# POWER-12V5V.net
KiCad netlist of a schematic drawn in EAGLE
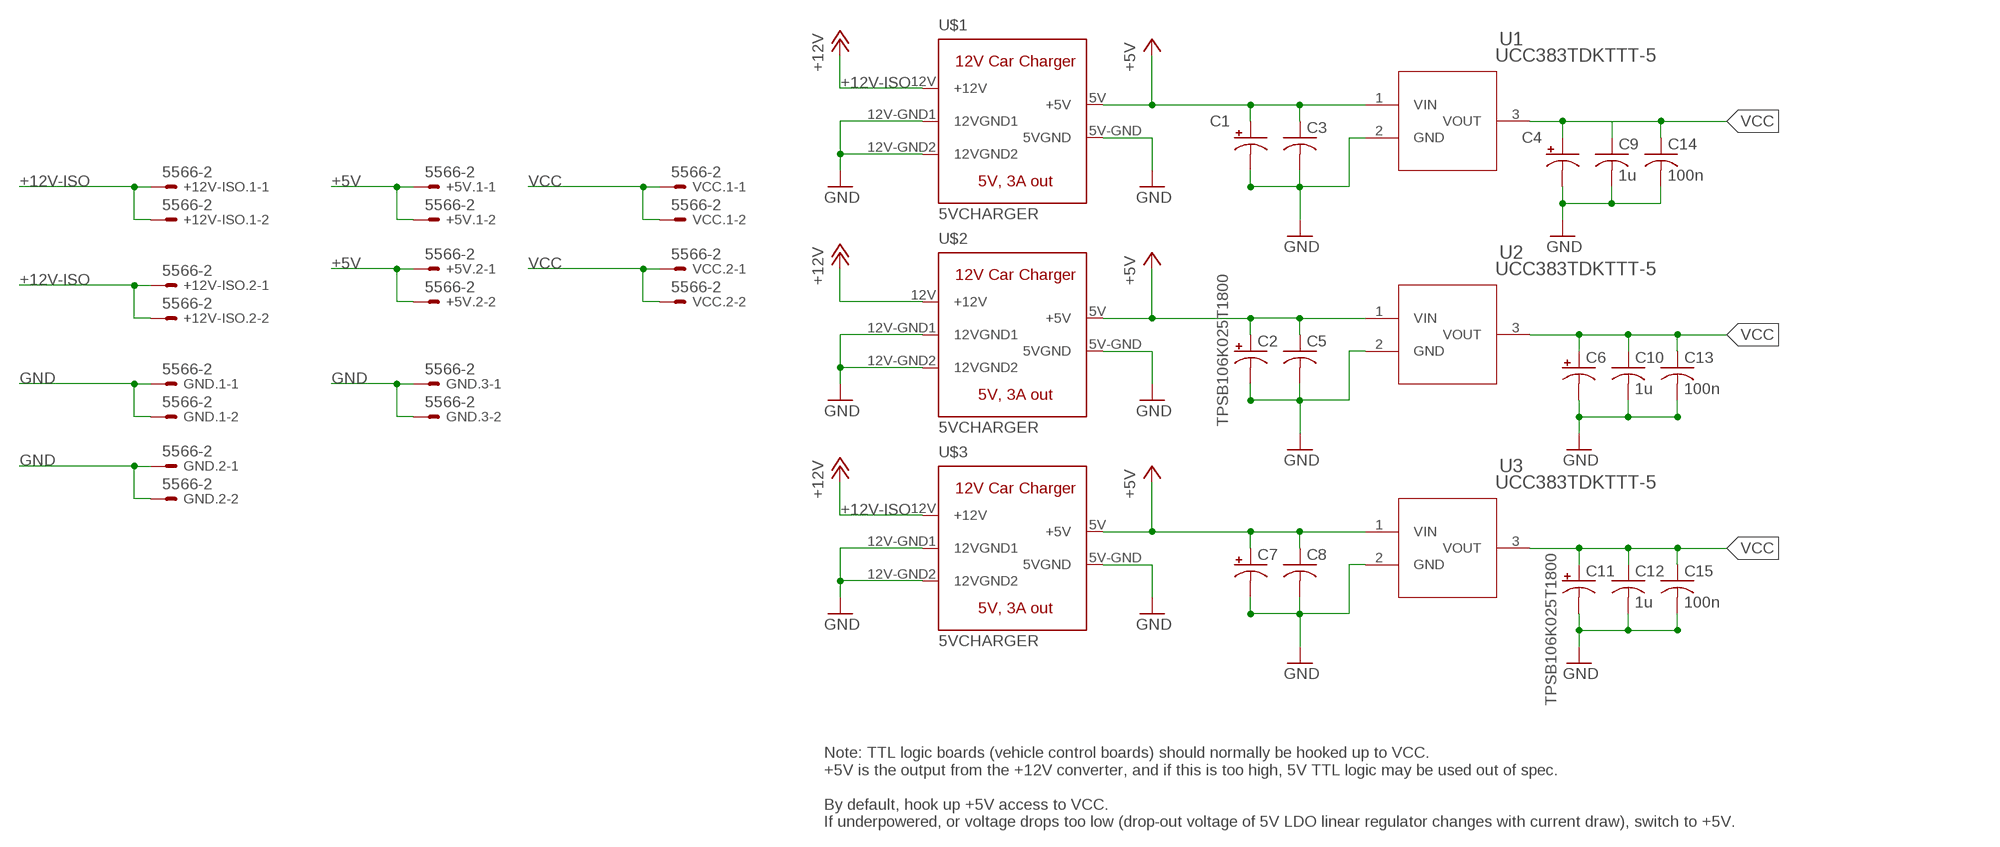
[diagram p0: schematic, sheet 1]

(export (version "E")
  (design (tool "Eeschema 10.0.6"))
  (components
    (comp (ref "+5V.1")
      (value "5566-2")
      (footprint "eagle-import:5566-2")
      (fields (field (name "MF") "MOLEX"))
      (libsource (lib "eagle-import") (part "5566-2"))
    )
    (comp (ref "+5V.2")
      (value "5566-2")
      (footprint "eagle-import:5566-2")
      (fields (field (name "MF") "MOLEX"))
      (libsource (lib "eagle-import") (part "5566-2"))
    )
    (comp (ref "+12V-ISO.1")
      (value "5566-2")
      (footprint "eagle-import:5566-2")
      (fields (field (name "MF") "MOLEX"))
      (libsource (lib "eagle-import") (part "5566-2"))
    )
    (comp (ref "+12V-ISO.2")
      (value "5566-2")
      (footprint "eagle-import:5566-2")
      (fields (field (name "MF") "MOLEX"))
      (libsource (lib "eagle-import") (part "5566-2"))
    )
    (comp (ref "C1")
      (value "TPSB106K025T1800")
      (footprint "eagle-import:DIONM3528X210N")
      (fields (field (name "MOUSER_PART_NUMBER") "581-TPSB106K025T1800"))
      (libsource (lib "eagle-import") (part "TPSB106K025T1800"))
    )
    (comp (ref "C2")
      (value "TPSB106K025T1800")
      (footprint "eagle-import:DIONM3528X210N")
      (fields (field (name "MOUSER_PART_NUMBER") "581-TPSB106K025T1800"))
      (libsource (lib "eagle-import") (part "TPSB106K025T1800"))
    )
    (comp (ref "C3")
      (value "C-USC0805")
      (footprint "eagle-import:C0805")
      (libsource (lib "eagle-import") (part "C-USC0805"))
    )
    (comp (ref "C4")
      (value "TPSB106K025T1800")
      (footprint "eagle-import:DIONM3528X210N")
      (fields (field (name "MOUSER_PART_NUMBER") "581-TPSB106K025T1800"))
      (libsource (lib "eagle-import") (part "TPSB106K025T1800"))
    )
    (comp (ref "C5")
      (value "C-USC0805")
      (footprint "eagle-import:C0805")
      (libsource (lib "eagle-import") (part "C-USC0805"))
    )
    (comp (ref "C6")
      (value "TPSB106K025T1800")
      (footprint "eagle-import:DIONM3528X210N")
      (fields (field (name "MOUSER_PART_NUMBER") "581-TPSB106K025T1800"))
      (libsource (lib "eagle-import") (part "TPSB106K025T1800"))
    )
    (comp (ref "C7")
      (value "TPSB106K025T1800")
      (footprint "eagle-import:DIONM3528X210N")
      (fields (field (name "MOUSER_PART_NUMBER") "581-TPSB106K025T1800"))
      (libsource (lib "eagle-import") (part "TPSB106K025T1800"))
    )
    (comp (ref "C8")
      (value "C-USC0805")
      (footprint "eagle-import:C0805")
      (libsource (lib "eagle-import") (part "C-USC0805"))
    )
    (comp (ref "C9")
      (value "1u")
      (footprint "eagle-import:C0805")
      (libsource (lib "eagle-import") (part "C-USC0805"))
    )
    (comp (ref "C10")
      (value "1u")
      (footprint "eagle-import:C0805")
      (libsource (lib "eagle-import") (part "C-USC0805"))
    )
    (comp (ref "C11")
      (value "TPSB106K025T1800")
      (footprint "eagle-import:DIONM3528X210N")
      (fields (field (name "MOUSER_PART_NUMBER") "581-TPSB106K025T1800"))
      (libsource (lib "eagle-import") (part "TPSB106K025T1800"))
    )
    (comp (ref "C12")
      (value "1u")
      (footprint "eagle-import:C0805")
      (libsource (lib "eagle-import") (part "C-USC0805"))
    )
    (comp (ref "C13")
      (value "100n")
      (footprint "eagle-import:C0805")
      (libsource (lib "eagle-import") (part "C-USC0805"))
    )
    (comp (ref "C14")
      (value "100n")
      (footprint "eagle-import:C0805")
      (libsource (lib "eagle-import") (part "C-USC0805"))
    )
    (comp (ref "C15")
      (value "100n")
      (footprint "eagle-import:C0805")
      (libsource (lib "eagle-import") (part "C-USC0805"))
    )
    (comp (ref "GND.1")
      (value "5566-2")
      (footprint "eagle-import:5566-2")
      (fields (field (name "MF") "MOLEX"))
      (libsource (lib "eagle-import") (part "5566-2"))
    )
    (comp (ref "GND.2")
      (value "5566-2")
      (footprint "eagle-import:5566-2")
      (fields (field (name "MF") "MOLEX"))
      (libsource (lib "eagle-import") (part "5566-2"))
    )
    (comp (ref "GND.3")
      (value "5566-2")
      (footprint "eagle-import:5566-2")
      (fields (field (name "MF") "MOLEX"))
      (libsource (lib "eagle-import") (part "5566-2"))
    )
    (comp (ref "U$1")
      (value "5VCHARGER")
      (footprint "eagle-import:5VCHARGER")
      (libsource (lib "eagle-import") (part "5VCHARGER"))
    )
    (comp (ref "U$2")
      (value "5VCHARGER")
      (footprint "eagle-import:5VCHARGER")
      (libsource (lib "eagle-import") (part "5VCHARGER"))
    )
    (comp (ref "U$3")
      (value "5VCHARGER")
      (footprint "eagle-import:5VCHARGER")
      (libsource (lib "eagle-import") (part "5VCHARGER"))
    )
    (comp (ref "U1")
      (value "UCC383TDKTTT-5")
      (footprint "eagle-import:TO263-3")
      (libsource (lib "eagle-import") (part "UCC383TDKTTT-5"))
    )
    (comp (ref "U2")
      (value "UCC383TDKTTT-5")
      (footprint "eagle-import:TO263-3")
      (libsource (lib "eagle-import") (part "UCC383TDKTTT-5"))
    )
    (comp (ref "U3")
      (value "UCC383TDKTTT-5")
      (footprint "eagle-import:TO263-3")
      (libsource (lib "eagle-import") (part "UCC383TDKTTT-5"))
    )
    (comp (ref "VCC.1")
      (value "5566-2")
      (footprint "eagle-import:5566-2")
      (fields (field (name "MF") "MOLEX"))
      (libsource (lib "eagle-import") (part "5566-2"))
    )
    (comp (ref "VCC.2")
      (value "5566-2")
      (footprint "eagle-import:5566-2")
      (fields (field (name "MF") "MOLEX"))
      (libsource (lib "eagle-import") (part "5566-2"))
    )
  )
  (nets
    (net (code "1") (name "+5V") (class "Default")
      (node (ref "+5V.1") (pin "1") (pinfunction "S_1") (pintype "passive"))
      (node (ref "+5V.1") (pin "2") (pinfunction "S_2") (pintype "passive"))
      (node (ref "+5V.2") (pin "1") (pinfunction "S_1") (pintype "passive"))
      (node (ref "+5V.2") (pin "2") (pinfunction "S_2") (pintype "passive"))
      (node (ref "C1") (pin "1") (pinfunction "+_1") (pintype "passive"))
      (node (ref "C2") (pin "1") (pinfunction "+_1") (pintype "passive"))
      (node (ref "C3") (pin "1") (pinfunction "1_1") (pintype "passive"))
      (node (ref "C5") (pin "1") (pinfunction "1_1") (pintype "passive"))
      (node (ref "C7") (pin "1") (pinfunction "+_1") (pintype "passive"))
      (node (ref "C8") (pin "1") (pinfunction "1_1") (pintype "passive"))
      (node (ref "U$1") (pin "5V") (pinfunction "+5V_5V") (pintype "input"))
      (node (ref "U$2") (pin "5V") (pinfunction "+5V_5V") (pintype "input"))
      (node (ref "U$3") (pin "5V") (pinfunction "+5V_5V") (pintype "input"))
      (node (ref "U1") (pin "1") (pinfunction "VIN_1") (pintype "input"))
      (node (ref "U2") (pin "1") (pinfunction "VIN_1") (pintype "input"))
      (node (ref "U3") (pin "1") (pinfunction "VIN_1") (pintype "input"))
    )
    (net (code "2") (name "+12V") (class "Default")
      (node (ref "+12V-ISO.1") (pin "1") (pinfunction "S_1") (pintype "passive"))
      (node (ref "+12V-ISO.1") (pin "2") (pinfunction "S_2") (pintype "passive"))
      (node (ref "+12V-ISO.2") (pin "1") (pinfunction "S_1") (pintype "passive"))
      (node (ref "+12V-ISO.2") (pin "2") (pinfunction "S_2") (pintype "passive"))
      (node (ref "U$1") (pin "12V") (pinfunction "+12V_12V") (pintype "passive"))
      (node (ref "U$2") (pin "12V") (pinfunction "+12V_12V") (pintype "passive"))
      (node (ref "U$3") (pin "12V") (pinfunction "+12V_12V") (pintype "passive"))
    )
    (net (code "3") (name "GND") (class "Default")
      (node (ref "C1") (pin "2") (pinfunction "-_2") (pintype "passive"))
      (node (ref "C10") (pin "2") (pinfunction "2_2") (pintype "passive"))
      (node (ref "C11") (pin "2") (pinfunction "-_2") (pintype "passive"))
      (node (ref "C12") (pin "2") (pinfunction "2_2") (pintype "passive"))
      (node (ref "C13") (pin "2") (pinfunction "2_2") (pintype "passive"))
      (node (ref "C14") (pin "2") (pinfunction "2_2") (pintype "passive"))
      (node (ref "C15") (pin "2") (pinfunction "2_2") (pintype "passive"))
      (node (ref "C2") (pin "2") (pinfunction "-_2") (pintype "passive"))
      (node (ref "C3") (pin "2") (pinfunction "2_2") (pintype "passive"))
      (node (ref "C4") (pin "2") (pinfunction "-_2") (pintype "passive"))
      (node (ref "C5") (pin "2") (pinfunction "2_2") (pintype "passive"))
      (node (ref "C6") (pin "2") (pinfunction "-_2") (pintype "passive"))
      (node (ref "C7") (pin "2") (pinfunction "-_2") (pintype "passive"))
      (node (ref "C8") (pin "2") (pinfunction "2_2") (pintype "passive"))
      (node (ref "C9") (pin "2") (pinfunction "2_2") (pintype "passive"))
      (node (ref "GND.1") (pin "1") (pinfunction "S_1") (pintype "passive"))
      (node (ref "GND.1") (pin "2") (pinfunction "S_2") (pintype "passive"))
      (node (ref "GND.2") (pin "1") (pinfunction "S_1") (pintype "passive"))
      (node (ref "GND.2") (pin "2") (pinfunction "S_2") (pintype "passive"))
      (node (ref "GND.3") (pin "1") (pinfunction "S_1") (pintype "passive"))
      (node (ref "GND.3") (pin "2") (pinfunction "S_2") (pintype "passive"))
      (node (ref "U$1") (pin "12V-GND1") (pinfunction "12VGND1_12V-GND1") (pintype "output"))
      (node (ref "U$1") (pin "12V-GND2") (pinfunction "12VGND2_12V-GND2") (pintype "power_in"))
      (node (ref "U$1") (pin "5V-GND") (pinfunction "5VGND_5V-GND") (pintype "input"))
      (node (ref "U$2") (pin "12V-GND1") (pinfunction "12VGND1_12V-GND1") (pintype "output"))
      (node (ref "U$2") (pin "12V-GND2") (pinfunction "12VGND2_12V-GND2") (pintype "power_in"))
      (node (ref "U$2") (pin "5V-GND") (pinfunction "5VGND_5V-GND") (pintype "input"))
      (node (ref "U$3") (pin "12V-GND1") (pinfunction "12VGND1_12V-GND1") (pintype "output"))
      (node (ref "U$3") (pin "12V-GND2") (pinfunction "12VGND2_12V-GND2") (pintype "power_in"))
      (node (ref "U$3") (pin "5V-GND") (pinfunction "5VGND_5V-GND") (pintype "input"))
      (node (ref "U1") (pin "2") (pinfunction "GND_2") (pintype "power_in"))
      (node (ref "U2") (pin "2") (pinfunction "GND_2") (pintype "power_in"))
      (node (ref "U3") (pin "2") (pinfunction "GND_2") (pintype "power_in"))
    )
    (net (code "4") (name "VCC") (class "Default")
      (node (ref "C10") (pin "1") (pinfunction "1_1") (pintype "passive"))
      (node (ref "C11") (pin "1") (pinfunction "+_1") (pintype "passive"))
      (node (ref "C12") (pin "1") (pinfunction "1_1") (pintype "passive"))
      (node (ref "C13") (pin "1") (pinfunction "1_1") (pintype "passive"))
      (node (ref "C14") (pin "1") (pinfunction "1_1") (pintype "passive"))
      (node (ref "C15") (pin "1") (pinfunction "1_1") (pintype "passive"))
      (node (ref "C4") (pin "1") (pinfunction "+_1") (pintype "passive"))
      (node (ref "C6") (pin "1") (pinfunction "+_1") (pintype "passive"))
      (node (ref "C9") (pin "1") (pinfunction "1_1") (pintype "passive"))
      (node (ref "U1") (pin "3") (pinfunction "VOUT_3") (pintype "output"))
      (node (ref "U2") (pin "3") (pinfunction "VOUT_3") (pintype "output"))
      (node (ref "U3") (pin "3") (pinfunction "VOUT_3") (pintype "output"))
      (node (ref "VCC.1") (pin "1") (pinfunction "S_1") (pintype "passive"))
      (node (ref "VCC.1") (pin "2") (pinfunction "S_2") (pintype "passive"))
      (node (ref "VCC.2") (pin "1") (pinfunction "S_1") (pintype "passive"))
      (node (ref "VCC.2") (pin "2") (pinfunction "S_2") (pintype "passive"))
    )
  )
)
